# Sensor_Bar_2_0_RGB_LED.net
KiCad netlist of a schematic drawn in Altium Designer
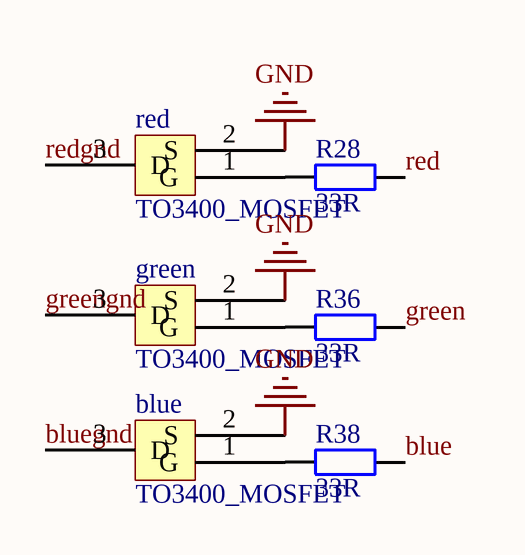
[diagram p0: Sensor Bar 2.0 RGB LED.SchDoc]

(export (version "E")
  (design (tool "Eeschema 10.0.6"))
  (components
    (comp (ref "blue")
      (value "TO3400_MOSFET")
      (footprint "npn")
      (libsource (lib "Small_lcd") (part "TO3400_MOSFET"))
    )
    (comp (ref "green")
      (value "TO3400_MOSFET")
      (footprint "npn")
      (libsource (lib "Small_lcd") (part "TO3400_MOSFET"))
    )
    (comp (ref "R28")
      (value "33R")
      (footprint "CR2012-0805")
      (description "Resistor")
      (fields (field (name "PUBLISHER") "Altium Limited"))
      (libsource (lib "Motorcontrol2.0") (part "Res2"))
    )
    (comp (ref "R36")
      (value "33R")
      (footprint "CR2012-0805")
      (description "Resistor")
      (fields (field (name "PUBLISHER") "Altium Limited"))
      (libsource (lib "Motorcontrol2.0") (part "Res2"))
    )
    (comp (ref "R38")
      (value "33R")
      (footprint "CR2012-0805")
      (description "Resistor")
      (fields (field (name "PUBLISHER") "Altium Limited"))
      (libsource (lib "Motorcontrol2.0") (part "Res2"))
    )
    (comp (ref "red")
      (value "TO3400_MOSFET")
      (footprint "npn")
      (libsource (lib "Small_lcd") (part "TO3400_MOSFET"))
    )
  )
  (nets
    (net (code "1") (name "/blue") (class "Default")
      (node (ref "R38") (pin "1") (pinfunction "1_1") (pintype "passive"))
    )
    (net (code "2") (name "/bluegnd") (class "Default")
      (node (ref "blue") (pin "3") (pinfunction "D_3") (pintype "passive"))
    )
    (net (code "3") (name "/green") (class "Default")
      (node (ref "R36") (pin "1") (pinfunction "1_1") (pintype "passive"))
    )
    (net (code "4") (name "/greengnd") (class "Default")
      (node (ref "green") (pin "3") (pinfunction "D_3") (pintype "passive"))
    )
    (net (code "5") (name "/red") (class "Default")
      (node (ref "R28") (pin "1") (pinfunction "1_1") (pintype "passive"))
    )
    (net (code "6") (name "/redgnd") (class "Default")
      (node (ref "red") (pin "3") (pinfunction "D_3") (pintype "passive"))
    )
    (net (code "7") (name "GND") (class "Default")
      (node (ref "blue") (pin "2") (pinfunction "S_2") (pintype "passive"))
      (node (ref "green") (pin "2") (pinfunction "S_2") (pintype "passive"))
      (node (ref "red") (pin "2") (pinfunction "S_2") (pintype "passive"))
    )
    (net (code "8") (name "Net-(blue-G)") (class "Default")
      (node (ref "R38") (pin "2") (pinfunction "2_2") (pintype "passive"))
      (node (ref "blue") (pin "1") (pinfunction "G_1") (pintype "passive"))
    )
    (net (code "9") (name "Net-(green-G)") (class "Default")
      (node (ref "R36") (pin "2") (pinfunction "2_2") (pintype "passive"))
      (node (ref "green") (pin "1") (pinfunction "G_1") (pintype "passive"))
    )
    (net (code "10") (name "Net-(red-G)") (class "Default")
      (node (ref "R28") (pin "2") (pinfunction "2_2") (pintype "passive"))
      (node (ref "red") (pin "1") (pinfunction "G_1") (pintype "passive"))
    )
  )
)
